# CuC.net
KiCad netlist of a schematic drawn in Altium Designer
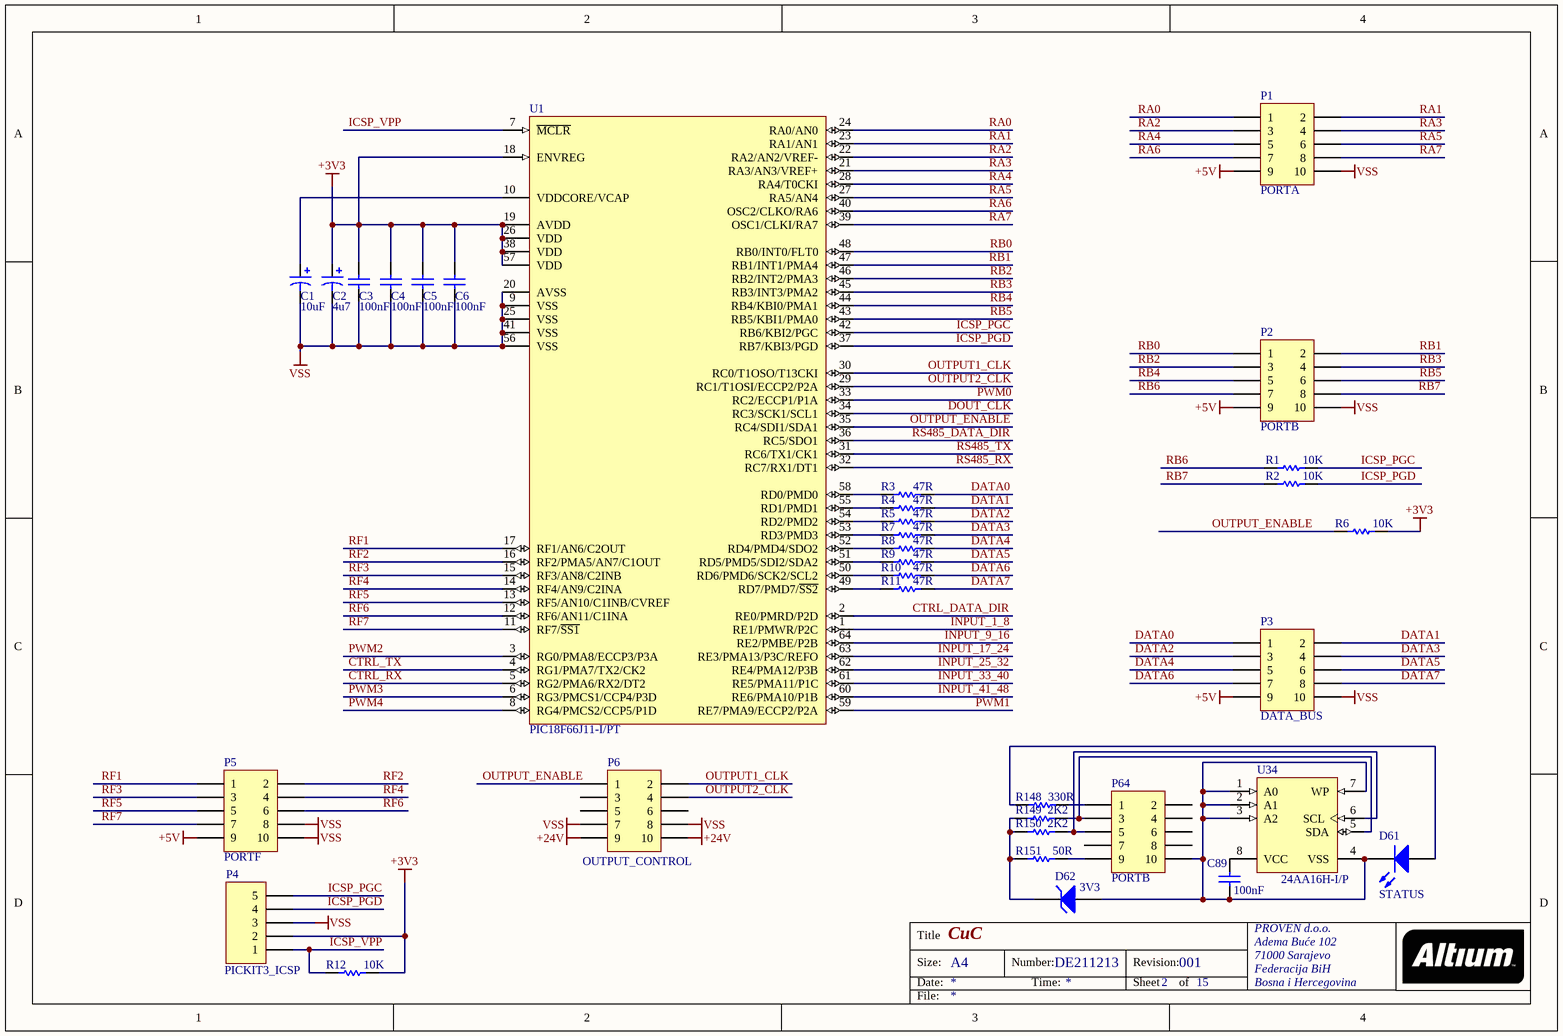
[diagram p0: CuC.SchDoc]

(export (version "E")
  (design (tool "Eeschema 10.0.6"))
  (components
    (comp (ref "C1")
      (value "10uF")
      (footprint "CAPPR1.5-4X7")
      (description "Aluminum Electrolytic Capacitor, Radial Style with Long Leads: 4.7uF, 63V")
      (fields (field (name "PUBLISHER") "Altium Limited"))
      (libsource (lib "Vishay Roederstein Electrolytic Radial-Lead Capacitor") (part "EKF00MM147J00"))
    )
    (comp (ref "C2")
      (value "4u7")
      (footprint "CAPPR1.5-4X7")
      (description "Aluminum Electrolytic Capacitor, Radial Style with Long Leads: 4.7uF, 63V")
      (fields (field (name "PUBLISHER") "Altium Limited"))
      (libsource (lib "Vishay Roederstein Electrolytic Radial-Lead Capacitor") (part "EKF00MM147J00"))
    )
    (comp (ref "C3")
      (value "100nF")
      (footprint "1206")
      (description "Ceramic Chip Capacitor - Standard")
      (fields (field (name "PUBLISHER") "Altium Limited"))
      (libsource (lib "KEMET Chip Capacitor") (part "C1206"))
    )
    (comp (ref "C4")
      (value "100nF")
      (footprint "1206")
      (description "Ceramic Chip Capacitor - Standard")
      (fields (field (name "PUBLISHER") "Altium Limited"))
      (libsource (lib "KEMET Chip Capacitor") (part "C1206"))
    )
    (comp (ref "C5")
      (value "100nF")
      (footprint "1206")
      (description "Ceramic Chip Capacitor - Standard")
      (fields (field (name "PUBLISHER") "Altium Limited"))
      (libsource (lib "KEMET Chip Capacitor") (part "C1206"))
    )
    (comp (ref "C6")
      (value "100nF")
      (footprint "1206")
      (description "Ceramic Chip Capacitor - Standard")
      (fields (field (name "PUBLISHER") "Altium Limited"))
      (libsource (lib "KEMET Chip Capacitor") (part "C1206"))
    )
    (comp (ref "C89")
      (value "100nF")
      (footprint "1206")
      (description "Ceramic Chip Capacitor - Standard")
      (fields (field (name "PUBLISHER") "Altium Limited"))
      (libsource (lib "KEMET Chip Capacitor") (part "C1206"))
    )
    (comp (ref "D61")
      (value "STATUS")
      (footprint "LED-0")
      (description "Typical INFRARED GaAs LED")
      (fields (field (name "PUBLISHER") "Altium Limited"))
      (libsource (lib "Miscellaneous Devices") (part "LED0"))
    )
    (comp (ref "D62")
      (value "3V3")
      (footprint "DIODE-0.7")
      (description "Zener Diode")
      (fields (field (name "PUBLISHER") "Altium Limited"))
      (libsource (lib "Miscellaneous Devices") (part "D Zener"))
    )
    (comp (ref "P1")
      (value "PORTA")
      (footprint "HDR2X5")
      (description "Header, 5-Pin, Dual row")
      (fields (field (name "PUBLISHER") "Altium Limited"))
      (libsource (lib "Miscellaneous Connectors") (part "Header 5X2"))
    )
    (comp (ref "P2")
      (value "PORTB")
      (footprint "HDR2X5")
      (description "Header, 5-Pin, Dual row")
      (fields (field (name "PUBLISHER") "Altium Limited"))
      (libsource (lib "Miscellaneous Connectors") (part "Header 5X2"))
    )
    (comp (ref "P3")
      (value "DATA_BUS")
      (footprint "HDR2X5")
      (description "Header, 5-Pin, Dual row")
      (fields (field (name "PUBLISHER") "Altium Limited"))
      (libsource (lib "Miscellaneous Connectors") (part "Header 5X2"))
    )
    (comp (ref "P4")
      (value "PICKIT3_ICSP")
      (footprint "HDR1X5")
      (description "Header, 5-Pin")
      (fields (field (name "PUBLISHER") "Altium Limited"))
      (libsource (lib "Miscellaneous Connectors") (part "Header 5"))
    )
    (comp (ref "P5")
      (value "PORTF")
      (footprint "HDR2X5")
      (description "Header, 5-Pin, Dual row")
      (fields (field (name "PUBLISHER") "Altium Limited"))
      (libsource (lib "Miscellaneous Connectors") (part "Header 5X2"))
    )
    (comp (ref "P6")
      (value "OUTPUT_CONTROL")
      (footprint "HDR2X5")
      (description "Header, 5-Pin, Dual row")
      (fields (field (name "PUBLISHER") "Altium Limited"))
      (libsource (lib "Miscellaneous Connectors") (part "Header 5X2"))
    )
    (comp (ref "P64")
      (value "PORTB")
      (footprint "HDR2X5")
      (description "Header, 5-Pin, Dual row")
      (fields (field (name "PUBLISHER") "Altium Limited"))
      (libsource (lib "Miscellaneous Connectors") (part "Header 5X2"))
    )
    (comp (ref "R1")
      (value "10K")
      (footprint "ERA-0603")
      (fields (field (name "PUBLISHER") "Altium Limited"))
      (libsource (lib "Panasonic Resistor") (part "ERA3Y"))
    )
    (comp (ref "R2")
      (value "10K")
      (footprint "ERA-0603")
      (fields (field (name "PUBLISHER") "Altium Limited"))
      (libsource (lib "Panasonic Resistor") (part "ERA3Y"))
    )
    (comp (ref "R3")
      (value "47R")
      (footprint "ERA-0603")
      (fields (field (name "PUBLISHER") "Altium Limited"))
      (libsource (lib "Panasonic Resistor") (part "ERA3Y"))
    )
    (comp (ref "R4")
      (value "47R")
      (footprint "ERA-0603")
      (fields (field (name "PUBLISHER") "Altium Limited"))
      (libsource (lib "Panasonic Resistor") (part "ERA3Y"))
    )
    (comp (ref "R5")
      (value "47R")
      (footprint "ERA-0603")
      (fields (field (name "PUBLISHER") "Altium Limited"))
      (libsource (lib "Panasonic Resistor") (part "ERA3Y"))
    )
    (comp (ref "R6")
      (value "10K")
      (footprint "ERA-0603")
      (fields (field (name "PUBLISHER") "Altium Limited"))
      (libsource (lib "Panasonic Resistor") (part "ERA3Y"))
    )
    (comp (ref "R7")
      (value "47R")
      (footprint "ERA-0603")
      (fields (field (name "PUBLISHER") "Altium Limited"))
      (libsource (lib "Panasonic Resistor") (part "ERA3Y"))
    )
    (comp (ref "R8")
      (value "47R")
      (footprint "ERA-0603")
      (fields (field (name "PUBLISHER") "Altium Limited"))
      (libsource (lib "Panasonic Resistor") (part "ERA3Y"))
    )
    (comp (ref "R9")
      (value "47R")
      (footprint "ERA-0603")
      (fields (field (name "PUBLISHER") "Altium Limited"))
      (libsource (lib "Panasonic Resistor") (part "ERA3Y"))
    )
    (comp (ref "R10")
      (value "47R")
      (footprint "ERA-0603")
      (fields (field (name "PUBLISHER") "Altium Limited"))
      (libsource (lib "Panasonic Resistor") (part "ERA3Y"))
    )
    (comp (ref "R11")
      (value "47R")
      (footprint "ERA-0603")
      (fields (field (name "PUBLISHER") "Altium Limited"))
      (libsource (lib "Panasonic Resistor") (part "ERA3Y"))
    )
    (comp (ref "R12")
      (value "10K")
      (footprint "ERA-0603")
      (fields (field (name "PUBLISHER") "Altium Limited"))
      (libsource (lib "Panasonic Resistor") (part "ERA3Y"))
    )
    (comp (ref "R148")
      (value "330R")
      (footprint "ERA-0603")
      (fields (field (name "PUBLISHER") "Altium Limited"))
      (libsource (lib "Panasonic Resistor") (part "ERA3Y"))
    )
    (comp (ref "R149")
      (value "2K2")
      (footprint "ERA-0603")
      (fields (field (name "PUBLISHER") "Altium Limited"))
      (libsource (lib "Panasonic Resistor") (part "ERA3Y"))
    )
    (comp (ref "R150")
      (value "2K2")
      (footprint "ERA-0603")
      (fields (field (name "PUBLISHER") "Altium Limited"))
      (libsource (lib "Panasonic Resistor") (part "ERA3Y"))
    )
    (comp (ref "R151")
      (value "50R")
      (footprint "ERA-0603")
      (fields (field (name "PUBLISHER") "Altium Limited"))
      (libsource (lib "Panasonic Resistor") (part "ERA3Y"))
    )
    (comp (ref "U1")
      (value "PIC18F66J11-I/PT")
      (footprint "TQFP-PT64_N")
      (fields (field (name "PUBLISHER") "Altium Limited"))
      (libsource (lib "Microchip Microcontroller 8-Bit PIC18") (part "PIC18F66J11-I/PT"))
    )
    (comp (ref "U34")
      (value "24AA16H-I/P")
      (footprint "PDIP300-P8")
      (description "16Kbit, 400kHz, 1.7V, I2C Serial EEPROM, 8-Pin PDIP, Industrial Temperature")
      (fields (field (name "PUBLISHER") "Altium Limited"))
      (libsource (lib "Microchip Memory I2C Serial EEPROM") (part "24AA16H-I/P"))
    )
  )
  (nets
    (net (code "1") (name "+3V3") (class "Default")
      (node (ref "C2") (pin "1") (pinfunction "1_1") (pintype "passive"))
      (node (ref "C3") (pin "1") (pinfunction "1_1") (pintype "passive"))
      (node (ref "C4") (pin "1") (pinfunction "1_1") (pintype "passive"))
      (node (ref "C5") (pin "1") (pinfunction "1_1") (pintype "passive"))
      (node (ref "C6") (pin "1") (pinfunction "1_1") (pintype "passive"))
      (node (ref "P4") (pin "2") (pinfunction "2_2") (pintype "passive"))
      (node (ref "R12") (pin "2") (pinfunction "2_2") (pintype "passive"))
      (node (ref "R6") (pin "2") (pinfunction "2_2") (pintype "passive"))
      (node (ref "U1") (pin "18") (pinfunction "ENVREG_18") (pintype "input"))
      (node (ref "U1") (pin "19") (pinfunction "AVDD_19") (pintype "power_in"))
      (node (ref "U1") (pin "26") (pinfunction "VDD_26") (pintype "power_in"))
      (node (ref "U1") (pin "38") (pinfunction "VDD_38") (pintype "power_in"))
      (node (ref "U1") (pin "57") (pinfunction "VDD_57") (pintype "power_in"))
    )
    (net (code "2") (name "+5V") (class "Default")
      (node (ref "P1") (pin "9") (pinfunction "9_9") (pintype "passive"))
      (node (ref "P2") (pin "9") (pinfunction "9_9") (pintype "passive"))
      (node (ref "P3") (pin "9") (pinfunction "9_9") (pintype "passive"))
      (node (ref "P5") (pin "9") (pinfunction "9_9") (pintype "passive"))
    )
    (net (code "3") (name "+24V") (class "Default")
      (node (ref "P6") (pin "10") (pinfunction "10_10") (pintype "passive"))
      (node (ref "P6") (pin "9") (pinfunction "9_9") (pintype "passive"))
    )
    (net (code "4") (name "/CTRL_DATA_DIR") (class "Default")
      (node (ref "U1") (pin "2") (pinfunction "RE0/PMRD/P2D_2") (pintype "bidirectional"))
    )
    (net (code "5") (name "/CTRL_RX") (class "Default")
      (node (ref "U1") (pin "5") (pinfunction "RG2/PMA6/RX2/DT2_5") (pintype "bidirectional"))
    )
    (net (code "6") (name "/CTRL_TX") (class "Default")
      (node (ref "U1") (pin "4") (pinfunction "RG1/PMA7/TX2/CK2_4") (pintype "bidirectional"))
    )
    (net (code "7") (name "/DATA0") (class "Default")
      (node (ref "P3") (pin "1") (pinfunction "1_1") (pintype "passive"))
      (node (ref "R3") (pin "2") (pinfunction "2_2") (pintype "passive"))
    )
    (net (code "8") (name "/DATA1") (class "Default")
      (node (ref "P3") (pin "2") (pinfunction "2_2") (pintype "passive"))
      (node (ref "R4") (pin "2") (pinfunction "2_2") (pintype "passive"))
    )
    (net (code "9") (name "/DATA2") (class "Default")
      (node (ref "P3") (pin "3") (pinfunction "3_3") (pintype "passive"))
      (node (ref "R5") (pin "2") (pinfunction "2_2") (pintype "passive"))
    )
    (net (code "10") (name "/DATA3") (class "Default")
      (node (ref "P3") (pin "4") (pinfunction "4_4") (pintype "passive"))
      (node (ref "R7") (pin "2") (pinfunction "2_2") (pintype "passive"))
    )
    (net (code "11") (name "/DATA4") (class "Default")
      (node (ref "P3") (pin "5") (pinfunction "5_5") (pintype "passive"))
      (node (ref "R8") (pin "2") (pinfunction "2_2") (pintype "passive"))
    )
    (net (code "12") (name "/DATA5") (class "Default")
      (node (ref "P3") (pin "6") (pinfunction "6_6") (pintype "passive"))
      (node (ref "R9") (pin "2") (pinfunction "2_2") (pintype "passive"))
    )
    (net (code "13") (name "/DATA6") (class "Default")
      (node (ref "P3") (pin "7") (pinfunction "7_7") (pintype "passive"))
      (node (ref "R10") (pin "2") (pinfunction "2_2") (pintype "passive"))
    )
    (net (code "14") (name "/DATA7") (class "Default")
      (node (ref "P3") (pin "8") (pinfunction "8_8") (pintype "passive"))
      (node (ref "R11") (pin "2") (pinfunction "2_2") (pintype "passive"))
    )
    (net (code "15") (name "/DOUT_CLK") (class "Default")
      (node (ref "U1") (pin "34") (pinfunction "RC3/SCK1/SCL1_34") (pintype "bidirectional"))
    )
    (net (code "16") (name "/ICSP_PGC") (class "Default")
      (node (ref "P4") (pin "5") (pinfunction "5_5") (pintype "passive"))
      (node (ref "R1") (pin "2") (pinfunction "2_2") (pintype "passive"))
      (node (ref "U1") (pin "42") (pinfunction "RB6/KBI2/PGC_42") (pintype "bidirectional"))
    )
    (net (code "17") (name "/ICSP_PGD") (class "Default")
      (node (ref "P4") (pin "4") (pinfunction "4_4") (pintype "passive"))
      (node (ref "R2") (pin "2") (pinfunction "2_2") (pintype "passive"))
      (node (ref "U1") (pin "37") (pinfunction "RB7/KBI3/PGD_37") (pintype "bidirectional"))
    )
    (net (code "18") (name "/ICSP_VPP") (class "Default")
      (node (ref "P4") (pin "1") (pinfunction "1_1") (pintype "passive"))
      (node (ref "R12") (pin "1") (pinfunction "1_1") (pintype "passive"))
      (node (ref "U1") (pin "7") (pinfunction "~{MCLR}_7") (pintype "input"))
    )
    (net (code "19") (name "/INPUT_1_8") (class "Default")
      (node (ref "U1") (pin "1") (pinfunction "RE1/PMWR/P2C_1") (pintype "bidirectional"))
    )
    (net (code "20") (name "/INPUT_9_16") (class "Default")
      (node (ref "U1") (pin "64") (pinfunction "RE2/PMBE/P2B_64") (pintype "bidirectional"))
    )
    (net (code "21") (name "/INPUT_17_24") (class "Default")
      (node (ref "U1") (pin "63") (pinfunction "RE3/PMA13/P3C/REFO_63") (pintype "bidirectional"))
    )
    (net (code "22") (name "/INPUT_25_32") (class "Default")
      (node (ref "U1") (pin "62") (pinfunction "RE4/PMA12/P3B_62") (pintype "bidirectional"))
    )
    (net (code "23") (name "/INPUT_33_40") (class "Default")
      (node (ref "U1") (pin "61") (pinfunction "RE5/PMA11/P1C_61") (pintype "bidirectional"))
    )
    (net (code "24") (name "/INPUT_41_48") (class "Default")
      (node (ref "U1") (pin "60") (pinfunction "RE6/PMA10/P1B_60") (pintype "bidirectional"))
    )
    (net (code "25") (name "/OUTPUT1_CLK") (class "Default")
      (node (ref "P6") (pin "2") (pinfunction "2_2") (pintype "passive"))
      (node (ref "U1") (pin "30") (pinfunction "RC0/T1OSO/T13CKI_30") (pintype "bidirectional"))
    )
    (net (code "26") (name "/OUTPUT2_CLK") (class "Default")
      (node (ref "P6") (pin "4") (pinfunction "4_4") (pintype "passive"))
      (node (ref "U1") (pin "29") (pinfunction "RC1/T1OSI/ECCP2/P2A_29") (pintype "bidirectional"))
    )
    (net (code "27") (name "/OUTPUT_ENABLE") (class "Default")
      (node (ref "P6") (pin "1") (pinfunction "1_1") (pintype "passive"))
      (node (ref "R6") (pin "1") (pinfunction "1_1") (pintype "passive"))
      (node (ref "U1") (pin "35") (pinfunction "RC4/SDI1/SDA1_35") (pintype "bidirectional"))
    )
    (net (code "28") (name "/PWM0") (class "Default")
      (node (ref "U1") (pin "33") (pinfunction "RC2/ECCP1/P1A_33") (pintype "bidirectional"))
    )
    (net (code "29") (name "/PWM1") (class "Default")
      (node (ref "U1") (pin "59") (pinfunction "RE7/PMA9/ECCP2/P2A_59") (pintype "bidirectional"))
    )
    (net (code "30") (name "/PWM2") (class "Default")
      (node (ref "U1") (pin "3") (pinfunction "RG0/PMA8/ECCP3/P3A_3") (pintype "bidirectional"))
    )
    (net (code "31") (name "/PWM3") (class "Default")
      (node (ref "U1") (pin "6") (pinfunction "RG3/PMCS1/CCP4/P3D_6") (pintype "bidirectional"))
    )
    (net (code "32") (name "/PWM4") (class "Default")
      (node (ref "U1") (pin "8") (pinfunction "RG4/PMCS2/CCP5/P1D_8") (pintype "bidirectional"))
    )
    (net (code "33") (name "/RA0") (class "Default")
      (node (ref "P1") (pin "1") (pinfunction "1_1") (pintype "passive"))
      (node (ref "U1") (pin "24") (pinfunction "RA0/AN0_24") (pintype "bidirectional"))
    )
    (net (code "34") (name "/RA1") (class "Default")
      (node (ref "P1") (pin "2") (pinfunction "2_2") (pintype "passive"))
      (node (ref "U1") (pin "23") (pinfunction "RA1/AN1_23") (pintype "bidirectional"))
    )
    (net (code "35") (name "/RA2") (class "Default")
      (node (ref "P1") (pin "3") (pinfunction "3_3") (pintype "passive"))
      (node (ref "U1") (pin "22") (pinfunction "RA2/AN2/VREF-_22") (pintype "bidirectional"))
    )
    (net (code "36") (name "/RA3") (class "Default")
      (node (ref "P1") (pin "4") (pinfunction "4_4") (pintype "passive"))
      (node (ref "U1") (pin "21") (pinfunction "RA3/AN3/VREF+_21") (pintype "bidirectional"))
    )
    (net (code "37") (name "/RA4") (class "Default")
      (node (ref "P1") (pin "5") (pinfunction "5_5") (pintype "passive"))
      (node (ref "U1") (pin "28") (pinfunction "RA4/T0CKI_28") (pintype "bidirectional"))
    )
    (net (code "38") (name "/RA5") (class "Default")
      (node (ref "P1") (pin "6") (pinfunction "6_6") (pintype "passive"))
      (node (ref "U1") (pin "27") (pinfunction "RA5/AN4_27") (pintype "bidirectional"))
    )
    (net (code "39") (name "/RA6") (class "Default")
      (node (ref "P1") (pin "7") (pinfunction "7_7") (pintype "passive"))
      (node (ref "U1") (pin "40") (pinfunction "OSC2/CLKO/RA6_40") (pintype "bidirectional"))
    )
    (net (code "40") (name "/RA7") (class "Default")
      (node (ref "P1") (pin "8") (pinfunction "8_8") (pintype "passive"))
      (node (ref "U1") (pin "39") (pinfunction "OSC1/CLKI/RA7_39") (pintype "bidirectional"))
    )
    (net (code "41") (name "/RB0") (class "Default")
      (node (ref "P2") (pin "1") (pinfunction "1_1") (pintype "passive"))
      (node (ref "U1") (pin "48") (pinfunction "RB0/INT0/FLT0_48") (pintype "bidirectional"))
    )
    (net (code "42") (name "/RB1") (class "Default")
      (node (ref "P2") (pin "2") (pinfunction "2_2") (pintype "passive"))
      (node (ref "U1") (pin "47") (pinfunction "RB1/INT1/PMA4_47") (pintype "bidirectional"))
    )
    (net (code "43") (name "/RB2") (class "Default")
      (node (ref "P2") (pin "3") (pinfunction "3_3") (pintype "passive"))
      (node (ref "U1") (pin "46") (pinfunction "RB2/INT2/PMA3_46") (pintype "bidirectional"))
    )
    (net (code "44") (name "/RB3") (class "Default")
      (node (ref "P2") (pin "4") (pinfunction "4_4") (pintype "passive"))
      (node (ref "U1") (pin "45") (pinfunction "RB3/INT3/PMA2_45") (pintype "bidirectional"))
    )
    (net (code "45") (name "/RB4") (class "Default")
      (node (ref "P2") (pin "5") (pinfunction "5_5") (pintype "passive"))
      (node (ref "U1") (pin "44") (pinfunction "RB4/KBI0/PMA1_44") (pintype "bidirectional"))
    )
    (net (code "46") (name "/RB5") (class "Default")
      (node (ref "P2") (pin "6") (pinfunction "6_6") (pintype "passive"))
      (node (ref "U1") (pin "43") (pinfunction "RB5/KBI1/PMA0_43") (pintype "bidirectional"))
    )
    (net (code "47") (name "/RB6") (class "Default")
      (node (ref "P2") (pin "7") (pinfunction "7_7") (pintype "passive"))
      (node (ref "R1") (pin "1") (pinfunction "1_1") (pintype "passive"))
    )
    (net (code "48") (name "/RB7") (class "Default")
      (node (ref "P2") (pin "8") (pinfunction "8_8") (pintype "passive"))
      (node (ref "R2") (pin "1") (pinfunction "1_1") (pintype "passive"))
    )
    (net (code "49") (name "/RF1") (class "Default")
      (node (ref "P5") (pin "1") (pinfunction "1_1") (pintype "passive"))
      (node (ref "U1") (pin "17") (pinfunction "RF1/AN6/C2OUT_17") (pintype "bidirectional"))
    )
    (net (code "50") (name "/RF2") (class "Default")
      (node (ref "P5") (pin "2") (pinfunction "2_2") (pintype "passive"))
      (node (ref "U1") (pin "16") (pinfunction "RF2/PMA5/AN7/C1OUT_16") (pintype "bidirectional"))
    )
    (net (code "51") (name "/RF3") (class "Default")
      (node (ref "P5") (pin "3") (pinfunction "3_3") (pintype "passive"))
      (node (ref "U1") (pin "15") (pinfunction "RF3/AN8/C2INB_15") (pintype "bidirectional"))
    )
    (net (code "52") (name "/RF4") (class "Default")
      (node (ref "P5") (pin "4") (pinfunction "4_4") (pintype "passive"))
      (node (ref "U1") (pin "14") (pinfunction "RF4/AN9/C2INA_14") (pintype "bidirectional"))
    )
    (net (code "53") (name "/RF5") (class "Default")
      (node (ref "P5") (pin "5") (pinfunction "5_5") (pintype "passive"))
      (node (ref "U1") (pin "13") (pinfunction "RF5/AN10/C1INB/CVREF_13") (pintype "bidirectional"))
    )
    (net (code "54") (name "/RF6") (class "Default")
      (node (ref "P5") (pin "6") (pinfunction "6_6") (pintype "passive"))
      (node (ref "U1") (pin "12") (pinfunction "RF6/AN11/C1INA_12") (pintype "bidirectional"))
    )
    (net (code "55") (name "/RF7") (class "Default")
      (node (ref "P5") (pin "7") (pinfunction "7_7") (pintype "passive"))
      (node (ref "U1") (pin "11") (pinfunction "RF7/~{SS1}_11") (pintype "bidirectional"))
    )
    (net (code "56") (name "/RS485_DATA_DIR") (class "Default")
      (node (ref "U1") (pin "36") (pinfunction "RC5/SDO1_36") (pintype "bidirectional"))
    )
    (net (code "57") (name "/RS485_RX") (class "Default")
      (node (ref "U1") (pin "32") (pinfunction "RC7/RX1/DT1_32") (pintype "bidirectional"))
    )
    (net (code "58") (name "/RS485_TX") (class "Default")
      (node (ref "U1") (pin "31") (pinfunction "RC6/TX1/CK1_31") (pintype "bidirectional"))
    )
    (net (code "59") (name "Net-(D61-A)") (class "Default")
      (node (ref "D61") (pin "1") (pinfunction "A_1") (pintype "passive"))
      (node (ref "R148") (pin "2") (pinfunction "2_2") (pintype "passive"))
    )
    (net (code "60") (name "Net-(D61-K)") (class "Default")
      (node (ref "C89") (pin "1") (pinfunction "1_1") (pintype "passive"))
      (node (ref "D61") (pin "2") (pinfunction "K_2") (pintype "passive"))
      (node (ref "D62") (pin "1") (pinfunction "A_1") (pintype "passive"))
      (node (ref "P64") (pin "10") (pinfunction "10_10") (pintype "passive"))
      (node (ref "U34") (pin "1") (pinfunction "A0_1") (pintype "input"))
      (node (ref "U34") (pin "2") (pinfunction "A1_2") (pintype "input"))
      (node (ref "U34") (pin "3") (pinfunction "A2_3") (pintype "input"))
      (node (ref "U34") (pin "4") (pinfunction "VSS_4") (pintype "power_in"))
      (node (ref "U34") (pin "7") (pinfunction "WP_7") (pintype "input"))
    )
    (net (code "61") (name "Net-(D62-K)") (class "Default")
      (node (ref "D62") (pin "2") (pinfunction "K_2") (pintype "passive"))
      (node (ref "R149") (pin "1") (pinfunction "1_1") (pintype "passive"))
      (node (ref "R150") (pin "1") (pinfunction "1_1") (pintype "passive"))
      (node (ref "R151") (pin "1") (pinfunction "1_1") (pintype "passive"))
    )
    (net (code "62") (name "Net-(P64-Pad1)") (class "Default")
      (node (ref "P64") (pin "1") (pinfunction "1_1") (pintype "passive"))
      (node (ref "R148") (pin "1") (pinfunction "1_1") (pintype "passive"))
    )
    (net (code "63") (name "Net-(P64-Pad9)") (class "Default")
      (node (ref "P64") (pin "9") (pinfunction "9_9") (pintype "passive"))
      (node (ref "R151") (pin "2") (pinfunction "2_2") (pintype "passive"))
    )
    (net (code "64") (name "Net-(U1-RD0{slash}PMD0)") (class "Default")
      (node (ref "R3") (pin "1") (pinfunction "1_1") (pintype "passive"))
      (node (ref "U1") (pin "58") (pinfunction "RD0/PMD0_58") (pintype "bidirectional"))
    )
    (net (code "65") (name "Net-(U1-RD1{slash}PMD1)") (class "Default")
      (node (ref "R4") (pin "1") (pinfunction "1_1") (pintype "passive"))
      (node (ref "U1") (pin "55") (pinfunction "RD1/PMD1_55") (pintype "bidirectional"))
    )
    (net (code "66") (name "Net-(U1-RD2{slash}PMD2)") (class "Default")
      (node (ref "R5") (pin "1") (pinfunction "1_1") (pintype "passive"))
      (node (ref "U1") (pin "54") (pinfunction "RD2/PMD2_54") (pintype "bidirectional"))
    )
    (net (code "67") (name "Net-(U1-RD3{slash}PMD3)") (class "Default")
      (node (ref "R7") (pin "1") (pinfunction "1_1") (pintype "passive"))
      (node (ref "U1") (pin "53") (pinfunction "RD3/PMD3_53") (pintype "bidirectional"))
    )
    (net (code "68") (name "Net-(U1-RD4{slash}PMD4{slash}SDO2)") (class "Default")
      (node (ref "R8") (pin "1") (pinfunction "1_1") (pintype "passive"))
      (node (ref "U1") (pin "52") (pinfunction "RD4/PMD4/SDO2_52") (pintype "bidirectional"))
    )
    (net (code "69") (name "Net-(U1-RD5{slash}PMD5{slash}SDI2{slash}SDA2)") (class "Default")
      (node (ref "R9") (pin "1") (pinfunction "1_1") (pintype "passive"))
      (node (ref "U1") (pin "51") (pinfunction "RD5/PMD5/SDI2/SDA2_51") (pintype "bidirectional"))
    )
    (net (code "70") (name "Net-(U1-RD6{slash}PMD6{slash}SCK2{slash}SCL2)") (class "Default")
      (node (ref "R10") (pin "1") (pinfunction "1_1") (pintype "passive"))
      (node (ref "U1") (pin "50") (pinfunction "RD6/PMD6/SCK2/SCL2_50") (pintype "bidirectional"))
    )
    (net (code "71") (name "Net-(U1-RD7{slash}PMD7{slash}~{SS2})") (class "Default")
      (node (ref "R11") (pin "1") (pinfunction "1_1") (pintype "passive"))
      (node (ref "U1") (pin "49") (pinfunction "RD7/PMD7/~{SS2}_49") (pintype "bidirectional"))
    )
    (net (code "72") (name "Net-(U1-VDDCORE{slash}VCAP)") (class "Default")
      (node (ref "C1") (pin "1") (pinfunction "1_1") (pintype "passive"))
      (node (ref "U1") (pin "10") (pinfunction "VDDCORE/VCAP_10") (pintype "power_in"))
    )
    (net (code "73") (name "Net-(U34-SCL)") (class "Default")
      (node (ref "P64") (pin "5") (pinfunction "5_5") (pintype "passive"))
      (node (ref "R150") (pin "2") (pinfunction "2_2") (pintype "passive"))
      (node (ref "U34") (pin "6") (pinfunction "SCL_6") (pintype "input"))
    )
    (net (code "74") (name "Net-(U34-SDA)") (class "Default")
      (node (ref "P64") (pin "3") (pinfunction "3_3") (pintype "passive"))
      (node (ref "R149") (pin "2") (pinfunction "2_2") (pintype "passive"))
      (node (ref "U34") (pin "5") (pinfunction "SDA_5") (pintype "bidirectional"))
    )
    (net (code "75") (name "Net-(U34-VCC)") (class "Default")
      (node (ref "C89") (pin "2") (pinfunction "2_2") (pintype "passive"))
      (node (ref "U34") (pin "8") (pinfunction "VCC_8") (pintype "power_in"))
    )
    (net (code "76") (name "VSS") (class "Default")
      (node (ref "C1") (pin "2") (pinfunction "2_2") (pintype "passive"))
      (node (ref "C2") (pin "2") (pinfunction "2_2") (pintype "passive"))
      (node (ref "C3") (pin "2") (pinfunction "2_2") (pintype "passive"))
      (node (ref "C4") (pin "2") (pinfunction "2_2") (pintype "passive"))
      (node (ref "C5") (pin "2") (pinfunction "2_2") (pintype "passive"))
      (node (ref "C6") (pin "2") (pinfunction "2_2") (pintype "passive"))
      (node (ref "P1") (pin "10") (pinfunction "10_10") (pintype "passive"))
      (node (ref "P2") (pin "10") (pinfunction "10_10") (pintype "passive"))
      (node (ref "P3") (pin "10") (pinfunction "10_10") (pintype "passive"))
      (node (ref "P4") (pin "3") (pinfunction "3_3") (pintype "passive"))
      (node (ref "P5") (pin "10") (pinfunction "10_10") (pintype "passive"))
      (node (ref "P5") (pin "8") (pinfunction "8_8") (pintype "passive"))
      (node (ref "P6") (pin "7") (pinfunction "7_7") (pintype "passive"))
      (node (ref "P6") (pin "8") (pinfunction "8_8") (pintype "passive"))
      (node (ref "U1") (pin "20") (pinfunction "AVSS_20") (pintype "power_in"))
      (node (ref "U1") (pin "25") (pinfunction "VSS_25") (pintype "power_in"))
      (node (ref "U1") (pin "41") (pinfunction "VSS_41") (pintype "power_in"))
      (node (ref "U1") (pin "56") (pinfunction "VSS_56") (pintype "power_in"))
      (node (ref "U1") (pin "9") (pinfunction "VSS_9") (pintype "power_in"))
    )
    (net (code "77") (name "unconnected-(P6-Pad3)") (class "Default")
      (node (ref "P6") (pin "3") (pinfunction "3_3") (pintype "passive"))
    )
    (net (code "78") (name "unconnected-(P6-Pad5)") (class "Default")
      (node (ref "P6") (pin "5") (pinfunction "5_5") (pintype "passive"))
    )
    (net (code "79") (name "unconnected-(P6-Pad6)") (class "Default")
      (node (ref "P6") (pin "6") (pinfunction "6_6") (pintype "passive"))
    )
    (net (code "80") (name "unconnected-(P64-Pad2)") (class "Default")
      (node (ref "P64") (pin "2") (pinfunction "2_2") (pintype "passive"))
    )
    (net (code "81") (name "unconnected-(P64-Pad4)") (class "Default")
      (node (ref "P64") (pin "4") (pinfunction "4_4") (pintype "passive"))
    )
    (net (code "82") (name "unconnected-(P64-Pad6)") (class "Default")
      (node (ref "P64") (pin "6") (pinfunction "6_6") (pintype "passive"))
    )
    (net (code "83") (name "unconnected-(P64-Pad7)") (class "Default")
      (node (ref "P64") (pin "7") (pinfunction "7_7") (pintype "passive"))
    )
    (net (code "84") (name "unconnected-(P64-Pad8)") (class "Default")
      (node (ref "P64") (pin "8") (pinfunction "8_8") (pintype "passive"))
    )
  )
)
